# Power.net
KiCad netlist of a schematic drawn in Altium Designer
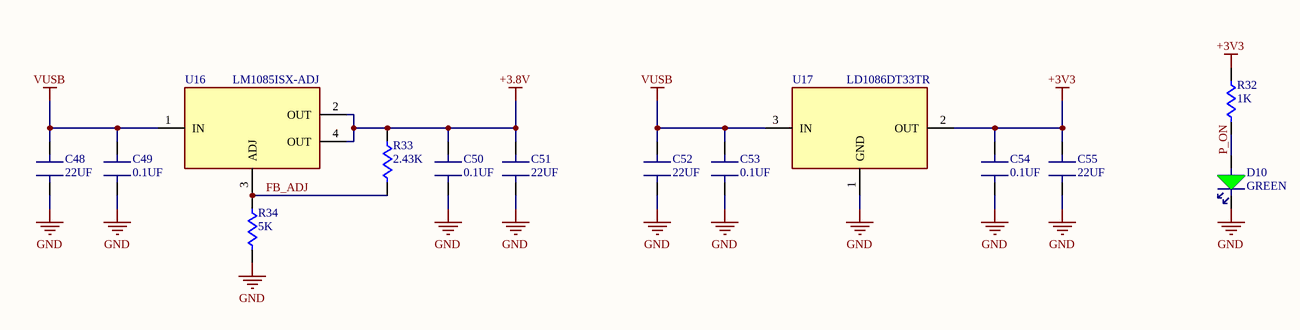
[diagram p0: Power.SchDoc]

(export (version "E")
  (design (tool "Eeschema 10.0.6"))
  (components
    (comp (ref "C48")
      (value "22UF")
      (footprint "CAP: 1206")
      (description "CAP SMD 1206")
      (libsource (lib "HZSchLib") (part "CAP 1206"))
    )
    (comp (ref "C49")
      (value "0.1UF")
      (footprint "CAP: 0603")
      (description "CAP SMD 0603")
      (libsource (lib "HZSchLib") (part "CAP 0603"))
    )
    (comp (ref "C50")
      (value "0.1UF")
      (footprint "CAP: 0603")
      (description "CAP SMD 0603")
      (libsource (lib "HZSchLib") (part "CAP 0603"))
    )
    (comp (ref "C51")
      (value "22UF")
      (footprint "CAP: 1206")
      (description "CAP SMD 1206")
      (libsource (lib "HZSchLib") (part "CAP 1206"))
    )
    (comp (ref "C52")
      (value "22UF")
      (footprint "CAP: 1206")
      (description "CAP SMD 1206")
      (libsource (lib "HZSchLib") (part "CAP 1206"))
    )
    (comp (ref "C53")
      (value "0.1UF")
      (footprint "CAP: 0603")
      (description "CAP SMD 0603")
      (libsource (lib "HZSchLib") (part "CAP 0603"))
    )
    (comp (ref "C54")
      (value "0.1UF")
      (footprint "CAP: 0603")
      (description "CAP SMD 0603")
      (libsource (lib "HZSchLib") (part "CAP 0603"))
    )
    (comp (ref "C55")
      (value "22UF")
      (footprint "CAP: 1206")
      (description "CAP SMD 1206")
      (libsource (lib "HZSchLib") (part "CAP 1206"))
    )
    (comp (ref "D10")
      (value "GREEN")
      (footprint "LED: 0603G")
      (description "LED GREEN CLEAR 0603 SMD")
      (libsource (lib "HZSchLib") (part "LED GREEN 0603"))
    )
    (comp (ref "R32")
      (value "1K")
      (footprint "RES: 0603")
      (description "RES SMD 0603")
      (libsource (lib "HZSchLib") (part "RES 0603"))
    )
    (comp (ref "R33")
      (value "2.43K")
      (footprint "RES: 0603")
      (description "RES SMD 0603")
      (libsource (lib "HZSchLib") (part "RES 0603"))
    )
    (comp (ref "R34")
      (value "5K")
      (footprint "RES: 0603")
      (description "RES SMD 0603")
      (libsource (lib "HZSchLib") (part "RES 0603"))
    )
    (comp (ref "U16")
      (value "LM1085ISX-ADJ")
      (footprint "TO263-3")
      (description "3-A, 29-V, linear voltage regulator 3-DDPAK/TO-263 -40 to 125")
      (fields
        (field (name "MANUFACTURER") "TI National Semiconductor")
        (field (name "MANUFACTURER PART NUMBER") "LM1085ISX-ADJ/NOPB")
      )
      (libsource (lib "HZSchLib") (part "LM1085ISX-ADJ/NOPB"))
    )
    (comp (ref "U17")
      (value "LD1086DT33TR")
      (footprint "DPAK")
      (description "IC REG LDO 3.3V 1.5A DPAK")
      (fields (field (name "MANUFACTURER") "STMicroelectronics"))
      (libsource (lib "HZSchLib") (part "LD1086DT33TR"))
    )
  )
  (nets
    (net (code "1") (name "+3.8V") (class "Default")
      (node (ref "C50") (pin "1") (pinfunction "A_1") (pintype "passive"))
      (node (ref "C51") (pin "2") (pinfunction "B_2") (pintype "passive"))
      (node (ref "R33") (pin "2") (pinfunction "2_2") (pintype "passive"))
      (node (ref "U16") (pin "2") (pinfunction "OUT_2") (pintype "passive"))
      (node (ref "U16") (pin "4") (pinfunction "OUT_4") (pintype "passive"))
    )
    (net (code "2") (name "+3V3") (class "Default")
      (node (ref "C54") (pin "1") (pinfunction "A_1") (pintype "passive"))
      (node (ref "C55") (pin "2") (pinfunction "B_2") (pintype "passive"))
      (node (ref "R32") (pin "2") (pinfunction "2_2") (pintype "passive"))
      (node (ref "U17") (pin "2") (pinfunction "OUT_2") (pintype "passive"))
    )
    (net (code "3") (name "/FB_ADJ") (class "Default")
      (node (ref "R33") (pin "1") (pinfunction "1_1") (pintype "passive"))
      (node (ref "R34") (pin "1") (pinfunction "1_1") (pintype "passive"))
      (node (ref "U16") (pin "3") (pinfunction "ADJ_3") (pintype "passive"))
    )
    (net (code "4") (name "/P_ON") (class "Default")
      (node (ref "D10") (pin "2") (pinfunction "A_2") (pintype "passive"))
      (node (ref "R32") (pin "1") (pinfunction "1_1") (pintype "passive"))
    )
    (net (code "5") (name "GND") (class "Default")
      (node (ref "C48") (pin "1") (pinfunction "A_1") (pintype "passive"))
      (node (ref "C49") (pin "2") (pinfunction "B_2") (pintype "passive"))
      (node (ref "C50") (pin "2") (pinfunction "B_2") (pintype "passive"))
      (node (ref "C51") (pin "1") (pinfunction "A_1") (pintype "passive"))
      (node (ref "C52") (pin "1") (pinfunction "A_1") (pintype "passive"))
      (node (ref "C53") (pin "2") (pinfunction "B_2") (pintype "passive"))
      (node (ref "C54") (pin "2") (pinfunction "B_2") (pintype "passive"))
      (node (ref "C55") (pin "1") (pinfunction "A_1") (pintype "passive"))
      (node (ref "D10") (pin "1") (pinfunction "C_1") (pintype "passive"))
      (node (ref "R34") (pin "2") (pinfunction "2_2") (pintype "passive"))
      (node (ref "U17") (pin "1") (pinfunction "GND_1") (pintype "passive"))
    )
    (net (code "6") (name "VUSB") (class "Default")
      (node (ref "C48") (pin "2") (pinfunction "B_2") (pintype "passive"))
      (node (ref "C49") (pin "1") (pinfunction "A_1") (pintype "passive"))
      (node (ref "C52") (pin "2") (pinfunction "B_2") (pintype "passive"))
      (node (ref "C53") (pin "1") (pinfunction "A_1") (pintype "passive"))
      (node (ref "U16") (pin "1") (pinfunction "IN_1") (pintype "passive"))
      (node (ref "U17") (pin "3") (pinfunction "IN_3") (pintype "passive"))
    )
  )
)
